# XT-02_Eyecillator_CEMC.net
KiCad netlist of a schematic drawn in EAGLE
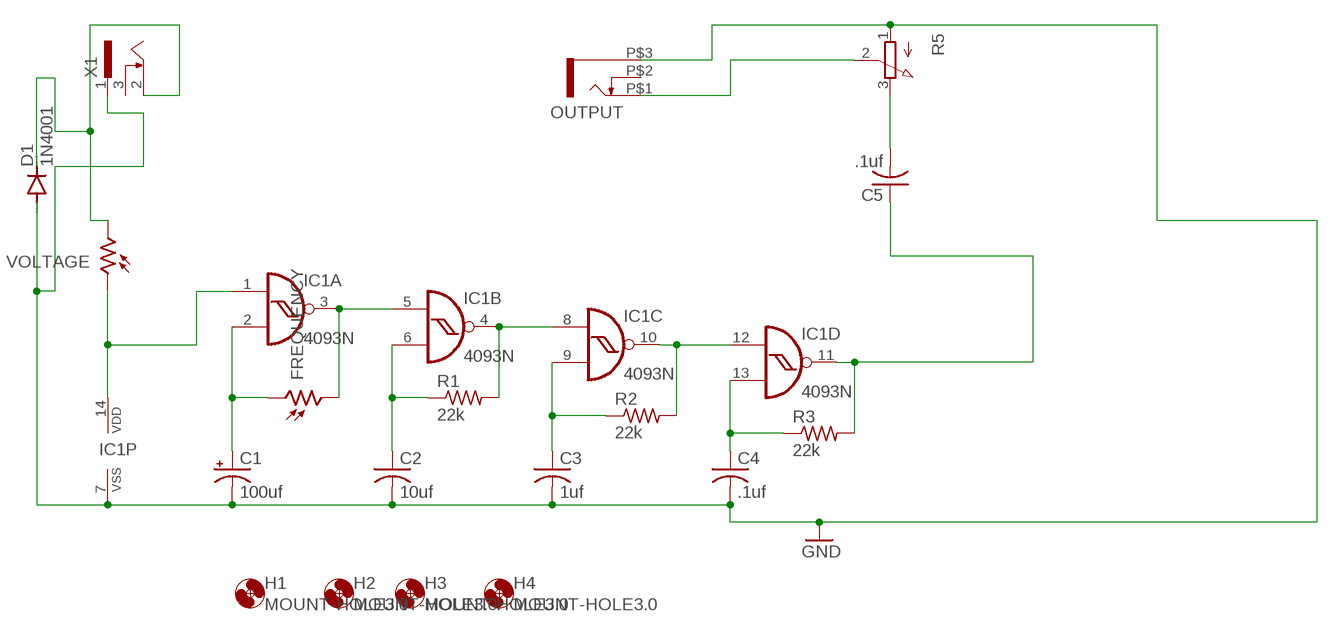
[diagram p0: schematic, sheet 1]

(export (version "E")
  (design (tool "Eeschema 10.0.6"))
  (components
    (comp (ref "C1")
      (value "100uf")
      (footprint "eagle-import:E2,5-6E")
      (libsource (lib "eagle-import") (part "CPOL-USE2,5-6E"))
    )
    (comp (ref "C2")
      (value "10uf")
      (footprint "eagle-import:C050-025X075")
      (libsource (lib "eagle-import") (part "C-US050-025X075"))
    )
    (comp (ref "C3")
      (value "1uf")
      (footprint "eagle-import:C050-025X075")
      (libsource (lib "eagle-import") (part "C-US050-025X075"))
    )
    (comp (ref "C4")
      (value ".1uf")
      (footprint "eagle-import:C050-025X075")
      (libsource (lib "eagle-import") (part "C-US050-025X075"))
    )
    (comp (ref "C5")
      (value ".1uf")
      (footprint "eagle-import:C050-025X075")
      (libsource (lib "eagle-import") (part "C-US050-025X075"))
    )
    (comp (ref "D1")
      (value "1N4001")
      (footprint "eagle-import:DO41-10")
      (libsource (lib "eagle-import") (part "1N4004"))
    )
    (comp (ref "FREQUENCY")
      (value "VT90N1")
      (footprint "eagle-import:VT900")
      (libsource (lib "eagle-import") (part "VT90N1"))
    )
    (comp (ref "H1")
      (value "MOUNT-HOLE3.0")
      (footprint "eagle-import:3,0")
      (libsource (lib "eagle-import") (part "MOUNT-HOLE3.0"))
    )
    (comp (ref "H2")
      (value "MOUNT-HOLE3.0")
      (footprint "eagle-import:3,0")
      (libsource (lib "eagle-import") (part "MOUNT-HOLE3.0"))
    )
    (comp (ref "H3")
      (value "MOUNT-HOLE3.0")
      (footprint "eagle-import:3,0")
      (libsource (lib "eagle-import") (part "MOUNT-HOLE3.0"))
    )
    (comp (ref "H4")
      (value "MOUNT-HOLE3.0")
      (footprint "eagle-import:3,0")
      (libsource (lib "eagle-import") (part "MOUNT-HOLE3.0"))
    )
    (comp (ref "IC1")
      (value "4093N")
      (footprint "eagle-import:DIL14")
      (libsource (lib "eagle-import") (part "4093N"))
    )
    (comp (ref "OUTPUT")
      (value "WQP-PJ301M-12_JACK")
      (footprint "eagle-import:WQP-PJ301M-12_JACK")
      (libsource (lib "eagle-import") (part "WQP-PJ301M-12_JACK"))
    )
    (comp (ref "R1")
      (value "22k")
      (footprint "eagle-import:0207_7")
      (libsource (lib "eagle-import") (part "R-US_0207/7"))
    )
    (comp (ref "R2")
      (value "22k")
      (footprint "eagle-import:0207_7")
      (libsource (lib "eagle-import") (part "R-US_0207/7"))
    )
    (comp (ref "R3")
      (value "22k")
      (footprint "eagle-import:0207_7")
      (libsource (lib "eagle-import") (part "R-US_0207/7"))
    )
    (comp (ref "R5")
      (value "EVUF2L")
      (footprint "eagle-import:EVUFXL")
      (libsource (lib "eagle-import") (part "EVULF2"))
    )
    (comp (ref "VOLTAGE")
      (value "VT90N1")
      (footprint "eagle-import:VT900")
      (libsource (lib "eagle-import") (part "VT90N1"))
    )
    (comp (ref "X1")
      (value "SCD-014A")
      (footprint "eagle-import:SCD-014-A")
      (libsource (lib "eagle-import") (part "SCD-014A"))
    )
  )
  (nets
    (net (code "1") (name "GND") (class "Default")
      (node (ref "C1") (pin "-") (pinfunction "-_-") (pintype "passive"))
      (node (ref "C2") (pin "2") (pinfunction "2_2") (pintype "passive"))
      (node (ref "C3") (pin "2") (pinfunction "2_2") (pintype "passive"))
      (node (ref "C4") (pin "2") (pinfunction "2_2") (pintype "passive"))
      (node (ref "D1") (pin "A") (pinfunction "A_A") (pintype "passive"))
      (node (ref "IC1") (pin "7") (pinfunction "VSS_7") (pintype "power_in"))
      (node (ref "OUTPUT") (pin "P$3") (pinfunction "1_P$3") (pintype "passive"))
      (node (ref "R5") (pin "1") (pinfunction "A_1") (pintype "passive"))
      (node (ref "X1") (pin "1") (pinfunction "1_1") (pintype "passive"))
    )
    (net (code "2") (name "Net-(D1-PadC)") (class "Default")
      (node (ref "D1") (pin "C") (pinfunction "C_C") (pintype "passive"))
      (node (ref "VOLTAGE") (pin "2") (pinfunction "2_2") (pintype "passive"))
      (node (ref "X1") (pin "2") (pinfunction "2_2") (pintype "passive"))
    )
    (net (code "3") (name "Net-(IC1A-I0)") (class "Default")
      (node (ref "IC1") (pin "1") (pinfunction "I0_1") (pintype "input"))
      (node (ref "IC1") (pin "14") (pinfunction "VDD_14") (pintype "power_in"))
      (node (ref "VOLTAGE") (pin "1") (pinfunction "1_1") (pintype "passive"))
    )
    (net (code "4") (name "Net-(IC1A-I1)") (class "Default")
      (node (ref "C1") (pin "+") (pinfunction "+_+") (pintype "passive"))
      (node (ref "FREQUENCY") (pin "1") (pinfunction "1_1") (pintype "passive"))
      (node (ref "IC1") (pin "2") (pinfunction "I1_2") (pintype "input"))
    )
    (net (code "5") (name "Net-(IC1A-O)") (class "Default")
      (node (ref "FREQUENCY") (pin "2") (pinfunction "2_2") (pintype "passive"))
      (node (ref "IC1") (pin "3") (pinfunction "O_3") (pintype "output"))
      (node (ref "IC1") (pin "5") (pinfunction "I0_5") (pintype "input"))
    )
    (net (code "6") (name "Net-(IC1B-I1)") (class "Default")
      (node (ref "C2") (pin "1") (pinfunction "1_1") (pintype "passive"))
      (node (ref "IC1") (pin "6") (pinfunction "I1_6") (pintype "input"))
      (node (ref "R1") (pin "1") (pinfunction "1_1") (pintype "passive"))
    )
    (net (code "7") (name "Net-(IC1B-O)") (class "Default")
      (node (ref "IC1") (pin "4") (pinfunction "O_4") (pintype "output"))
      (node (ref "IC1") (pin "8") (pinfunction "I0_8") (pintype "input"))
      (node (ref "R1") (pin "2") (pinfunction "2_2") (pintype "passive"))
    )
    (net (code "8") (name "Net-(IC1C-I1)") (class "Default")
      (node (ref "C3") (pin "1") (pinfunction "1_1") (pintype "passive"))
      (node (ref "IC1") (pin "9") (pinfunction "I1_9") (pintype "input"))
      (node (ref "R2") (pin "1") (pinfunction "1_1") (pintype "passive"))
    )
    (net (code "9") (name "Net-(IC1C-O)") (class "Default")
      (node (ref "IC1") (pin "10") (pinfunction "O_10") (pintype "output"))
      (node (ref "IC1") (pin "12") (pinfunction "I0_12") (pintype "input"))
      (node (ref "R2") (pin "2") (pinfunction "2_2") (pintype "passive"))
    )
    (net (code "10") (name "Net-(IC1D-I1)") (class "Default")
      (node (ref "C4") (pin "1") (pinfunction "1_1") (pintype "passive"))
      (node (ref "IC1") (pin "13") (pinfunction "I1_13") (pintype "input"))
      (node (ref "R3") (pin "1") (pinfunction "1_1") (pintype "passive"))
    )
    (net (code "11") (name "Net-(IC1D-O)") (class "Default")
      (node (ref "C5") (pin "1") (pinfunction "1_1") (pintype "passive"))
      (node (ref "IC1") (pin "11") (pinfunction "O_11") (pintype "output"))
      (node (ref "R3") (pin "2") (pinfunction "2_2") (pintype "passive"))
    )
    (net (code "12") (name "Net-(OUTPUT-2)") (class "Default")
      (node (ref "OUTPUT") (pin "P$1") (pinfunction "2_P$1") (pintype "passive"))
      (node (ref "R5") (pin "2") (pinfunction "S_2") (pintype "passive"))
    )
    (net (code "13") (name "Net-(R5-E)") (class "Default")
      (node (ref "C5") (pin "2") (pinfunction "2_2") (pintype "passive"))
      (node (ref "R5") (pin "3") (pinfunction "E_3") (pintype "passive"))
    )
    (net (code "14") (name "unconnected-(OUTPUT-3-PadP$2)") (class "Default")
      (node (ref "OUTPUT") (pin "P$2") (pinfunction "3_P$2") (pintype "passive"))
    )
    (net (code "15") (name "unconnected-(X1-Pad3)") (class "Default")
      (node (ref "X1") (pin "3") (pinfunction "3_3") (pintype "passive"))
    )
  )
)
